# ind_output.net
KiCad netlist of a schematic drawn in EAGLE
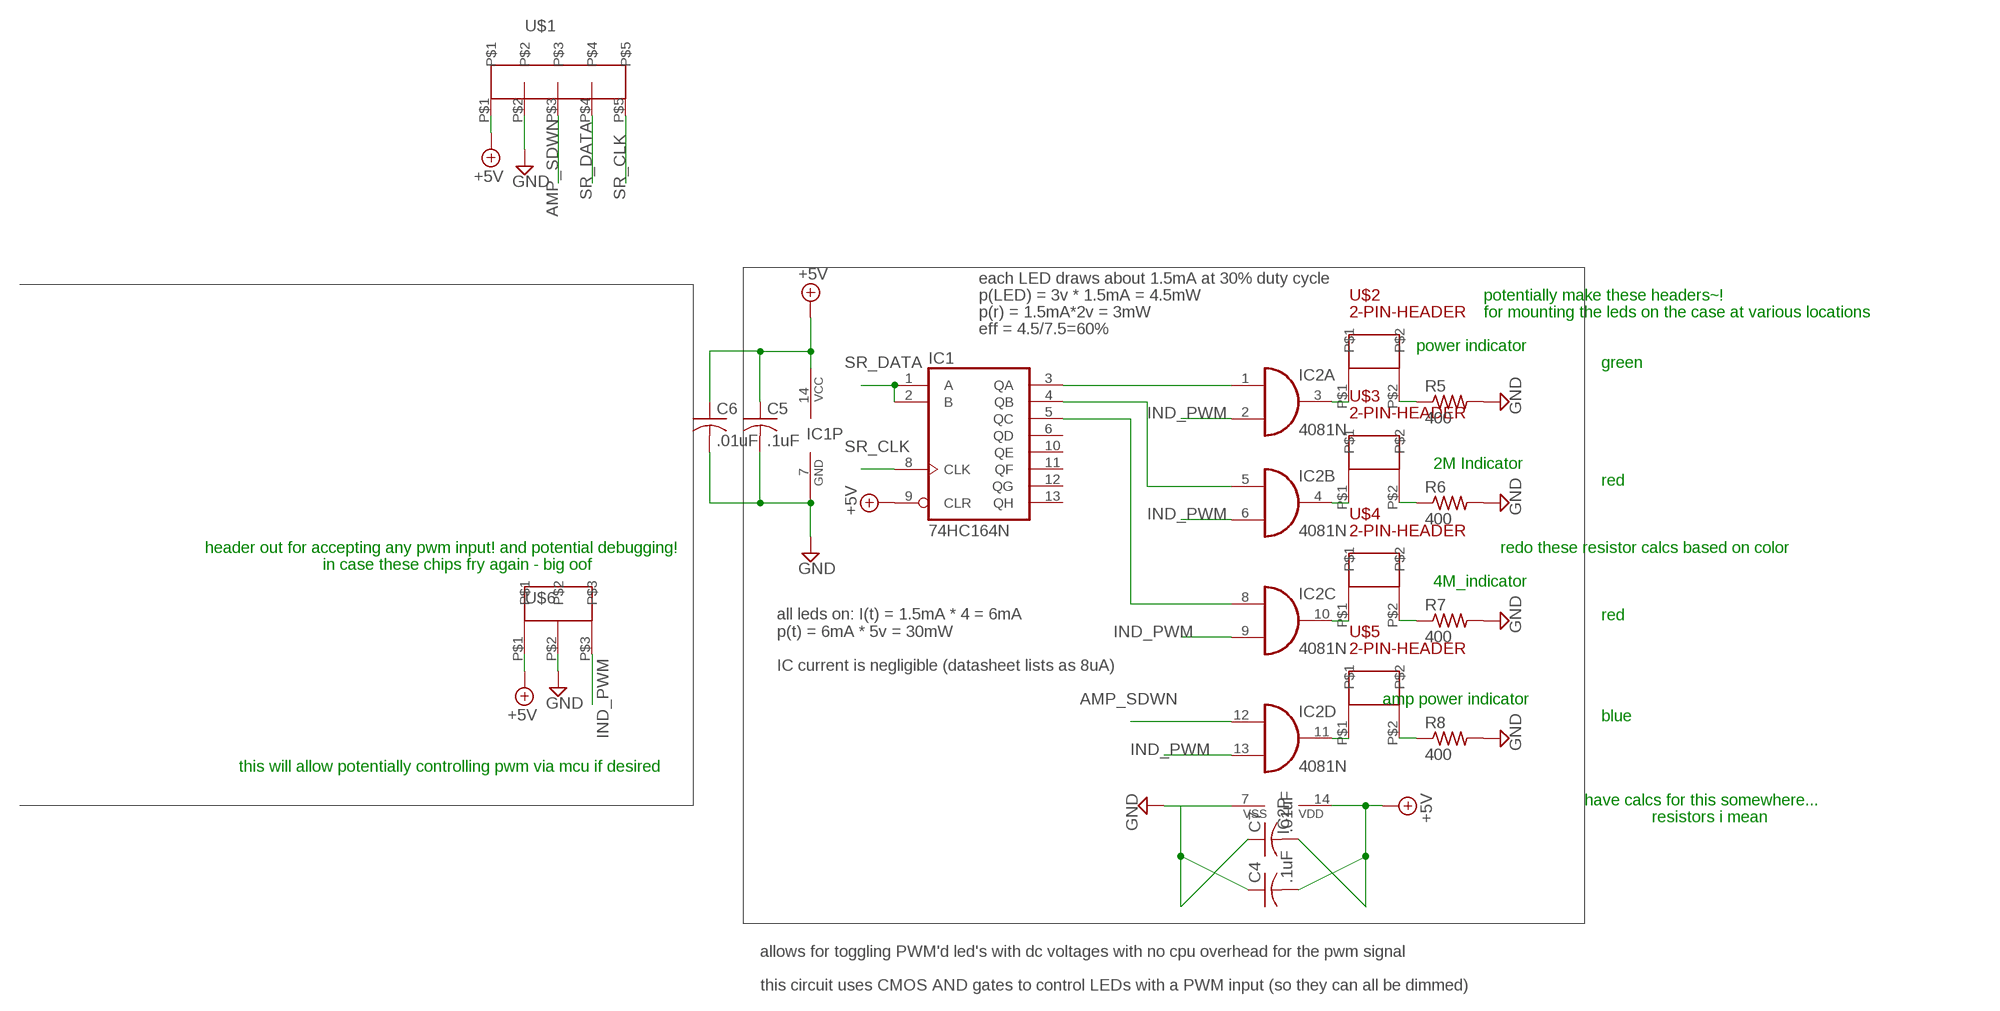
[diagram p0: schematic, sheet 1]

(export (version "E")
  (design (tool "Eeschema 10.0.6"))
  (components
    (comp (ref "C4")
      (value ".1uF")
      (footprint "eagle-import:C025-030X050")
      (libsource (lib "eagle-import") (part "C-US025-030X050"))
    )
    (comp (ref "C5")
      (value ".1uF")
      (footprint "eagle-import:C025-030X050")
      (libsource (lib "eagle-import") (part "C-US025-030X050"))
    )
    (comp (ref "C6")
      (value ".01uF")
      (footprint "eagle-import:C025-030X050")
      (libsource (lib "eagle-import") (part "C-US025-030X050"))
    )
    (comp (ref "C7")
      (value ".01uF")
      (footprint "eagle-import:C025-030X050")
      (libsource (lib "eagle-import") (part "C-US025-030X050"))
    )
    (comp (ref "IC1")
      (value "74HC164N")
      (footprint "eagle-import:DIL14")
      (libsource (lib "eagle-import") (part "74164NHC"))
    )
    (comp (ref "IC2")
      (value "4081N")
      (footprint "eagle-import:DIL14")
      (libsource (lib "eagle-import") (part "4081N"))
    )
    (comp (ref "R5")
      (value "400")
      (footprint "eagle-import:0204_7")
      (libsource (lib "eagle-import") (part "R-US_0204/7"))
    )
    (comp (ref "R6")
      (value "400")
      (footprint "eagle-import:0204_7")
      (libsource (lib "eagle-import") (part "R-US_0204/7"))
    )
    (comp (ref "R7")
      (value "400")
      (footprint "eagle-import:0204_7")
      (libsource (lib "eagle-import") (part "R-US_0204/7"))
    )
    (comp (ref "R8")
      (value "400")
      (footprint "eagle-import:0204_7")
      (libsource (lib "eagle-import") (part "R-US_0204/7"))
    )
    (comp (ref "U$1")
      (value "5-PIN-HEADER")
      (footprint "eagle-import:5-PIN-HEADER")
      (libsource (lib "eagle-import") (part "5-PIN-HEADER"))
    )
    (comp (ref "U$2")
      (value "2-PIN-HEADER")
      (footprint "eagle-import:2-PIN-HEADER")
      (libsource (lib "eagle-import") (part "2-PIN-HEADER"))
    )
    (comp (ref "U$3")
      (value "2-PIN-HEADER")
      (footprint "eagle-import:2-PIN-HEADER")
      (libsource (lib "eagle-import") (part "2-PIN-HEADER"))
    )
    (comp (ref "U$4")
      (value "2-PIN-HEADER")
      (footprint "eagle-import:2-PIN-HEADER")
      (libsource (lib "eagle-import") (part "2-PIN-HEADER"))
    )
    (comp (ref "U$5")
      (value "2-PIN-HEADER")
      (footprint "eagle-import:2-PIN-HEADER")
      (libsource (lib "eagle-import") (part "2-PIN-HEADER"))
    )
    (comp (ref "U$6")
      (value "3-PIN-HEADER")
      (footprint "eagle-import:3-PIN-HEADER")
      (libsource (lib "eagle-import") (part "3-PIN-HEADER"))
    )
  )
  (nets
    (net (code "1") (name "+5V") (class "Default")
      (node (ref "C4") (pin "2") (pinfunction "2_2") (pintype "passive"))
      (node (ref "C5") (pin "1") (pinfunction "1_1") (pintype "passive"))
      (node (ref "C6") (pin "1") (pinfunction "1_1") (pintype "passive"))
      (node (ref "C7") (pin "2") (pinfunction "2_2") (pintype "passive"))
      (node (ref "IC1") (pin "14") (pinfunction "VCC_14") (pintype "power_in"))
      (node (ref "IC1") (pin "9") (pinfunction "CLR_9") (pintype "input"))
      (node (ref "IC2") (pin "14") (pinfunction "VDD_14") (pintype "power_in"))
      (node (ref "U$1") (pin "P$1") (pinfunction "P$1_P$1") (pintype "bidirectional"))
      (node (ref "U$6") (pin "P$1") (pinfunction "P$1_P$1") (pintype "bidirectional"))
    )
    (net (code "2") (name "/AMP_SDWN") (class "Default")
      (node (ref "IC2") (pin "12") (pinfunction "I0_12") (pintype "input"))
      (node (ref "U$1") (pin "P$3") (pinfunction "P$3_P$3") (pintype "bidirectional"))
    )
    (net (code "3") (name "/IND_PWM") (class "Default")
      (node (ref "IC2") (pin "13") (pinfunction "I1_13") (pintype "input"))
      (node (ref "IC2") (pin "2") (pinfunction "I1_2") (pintype "input"))
      (node (ref "IC2") (pin "6") (pinfunction "I1_6") (pintype "input"))
      (node (ref "IC2") (pin "9") (pinfunction "I1_9") (pintype "input"))
      (node (ref "U$6") (pin "P$3") (pinfunction "P$3_P$3") (pintype "bidirectional"))
    )
    (net (code "4") (name "/SR_CLK") (class "Default")
      (node (ref "IC1") (pin "8") (pinfunction "CLK_8") (pintype "input"))
      (node (ref "U$1") (pin "P$5") (pinfunction "P$5_P$5") (pintype "bidirectional"))
    )
    (net (code "5") (name "/SR_DATA") (class "Default")
      (node (ref "IC1") (pin "1") (pinfunction "A_1") (pintype "input"))
      (node (ref "IC1") (pin "2") (pinfunction "B_2") (pintype "input"))
      (node (ref "U$1") (pin "P$4") (pinfunction "P$4_P$4") (pintype "bidirectional"))
    )
    (net (code "6") (name "GND") (class "Default")
      (node (ref "C4") (pin "1") (pinfunction "1_1") (pintype "passive"))
      (node (ref "C5") (pin "2") (pinfunction "2_2") (pintype "passive"))
      (node (ref "C6") (pin "2") (pinfunction "2_2") (pintype "passive"))
      (node (ref "C7") (pin "1") (pinfunction "1_1") (pintype "passive"))
      (node (ref "IC1") (pin "7") (pinfunction "GND_7") (pintype "power_in"))
      (node (ref "IC2") (pin "7") (pinfunction "VSS_7") (pintype "power_in"))
      (node (ref "R5") (pin "2") (pinfunction "2_2") (pintype "passive"))
      (node (ref "R6") (pin "2") (pinfunction "2_2") (pintype "passive"))
      (node (ref "R7") (pin "2") (pinfunction "2_2") (pintype "passive"))
      (node (ref "R8") (pin "2") (pinfunction "2_2") (pintype "passive"))
      (node (ref "U$1") (pin "P$2") (pinfunction "P$2_P$2") (pintype "bidirectional"))
      (node (ref "U$6") (pin "P$2") (pinfunction "P$2_P$2") (pintype "bidirectional"))
    )
    (net (code "7") (name "Net-(IC1A-QA)") (class "Default")
      (node (ref "IC1") (pin "3") (pinfunction "QA_3") (pintype "output"))
      (node (ref "IC2") (pin "1") (pinfunction "I0_1") (pintype "input"))
    )
    (net (code "8") (name "Net-(IC1A-QB)") (class "Default")
      (node (ref "IC1") (pin "4") (pinfunction "QB_4") (pintype "output"))
      (node (ref "IC2") (pin "5") (pinfunction "I0_5") (pintype "input"))
    )
    (net (code "9") (name "Net-(IC1A-QC)") (class "Default")
      (node (ref "IC1") (pin "5") (pinfunction "QC_5") (pintype "output"))
      (node (ref "IC2") (pin "8") (pinfunction "I0_8") (pintype "input"))
    )
    (net (code "10") (name "Net-(IC2A-O)") (class "Default")
      (node (ref "IC2") (pin "3") (pinfunction "O_3") (pintype "output"))
      (node (ref "U$2") (pin "P$1") (pinfunction "P$1_P$1") (pintype "bidirectional"))
    )
    (net (code "11") (name "Net-(IC2B-O)") (class "Default")
      (node (ref "IC2") (pin "4") (pinfunction "O_4") (pintype "output"))
      (node (ref "U$3") (pin "P$1") (pinfunction "P$1_P$1") (pintype "bidirectional"))
    )
    (net (code "12") (name "Net-(IC2C-O)") (class "Default")
      (node (ref "IC2") (pin "10") (pinfunction "O_10") (pintype "output"))
      (node (ref "U$4") (pin "P$1") (pinfunction "P$1_P$1") (pintype "bidirectional"))
    )
    (net (code "13") (name "Net-(IC2D-O)") (class "Default")
      (node (ref "IC2") (pin "11") (pinfunction "O_11") (pintype "output"))
      (node (ref "U$5") (pin "P$1") (pinfunction "P$1_P$1") (pintype "bidirectional"))
    )
    (net (code "14") (name "Net-(R5-Pad1)") (class "Default")
      (node (ref "R5") (pin "1") (pinfunction "1_1") (pintype "passive"))
      (node (ref "U$2") (pin "P$2") (pinfunction "P$2_P$2") (pintype "bidirectional"))
    )
    (net (code "15") (name "Net-(R6-Pad1)") (class "Default")
      (node (ref "R6") (pin "1") (pinfunction "1_1") (pintype "passive"))
      (node (ref "U$3") (pin "P$2") (pinfunction "P$2_P$2") (pintype "bidirectional"))
    )
    (net (code "16") (name "Net-(R7-Pad1)") (class "Default")
      (node (ref "R7") (pin "1") (pinfunction "1_1") (pintype "passive"))
      (node (ref "U$4") (pin "P$2") (pinfunction "P$2_P$2") (pintype "bidirectional"))
    )
    (net (code "17") (name "Net-(R8-Pad1)") (class "Default")
      (node (ref "R8") (pin "1") (pinfunction "1_1") (pintype "passive"))
      (node (ref "U$5") (pin "P$2") (pinfunction "P$2_P$2") (pintype "bidirectional"))
    )
    (net (code "18") (name "unconnected-(IC1A-QD-Pad6)") (class "Default")
      (node (ref "IC1") (pin "6") (pinfunction "QD_6") (pintype "output"))
    )
    (net (code "19") (name "unconnected-(IC1A-QE-Pad10)") (class "Default")
      (node (ref "IC1") (pin "10") (pinfunction "QE_10") (pintype "output"))
    )
    (net (code "20") (name "unconnected-(IC1A-QF-Pad11)") (class "Default")
      (node (ref "IC1") (pin "11") (pinfunction "QF_11") (pintype "output"))
    )
    (net (code "21") (name "unconnected-(IC1A-QG-Pad12)") (class "Default")
      (node (ref "IC1") (pin "12") (pinfunction "QG_12") (pintype "output"))
    )
    (net (code "22") (name "unconnected-(IC1A-QH-Pad13)") (class "Default")
      (node (ref "IC1") (pin "13") (pinfunction "QH_13") (pintype "output"))
    )
  )
)
